# 05-USB-UART.net
KiCad netlist of a schematic drawn in Altium Designer
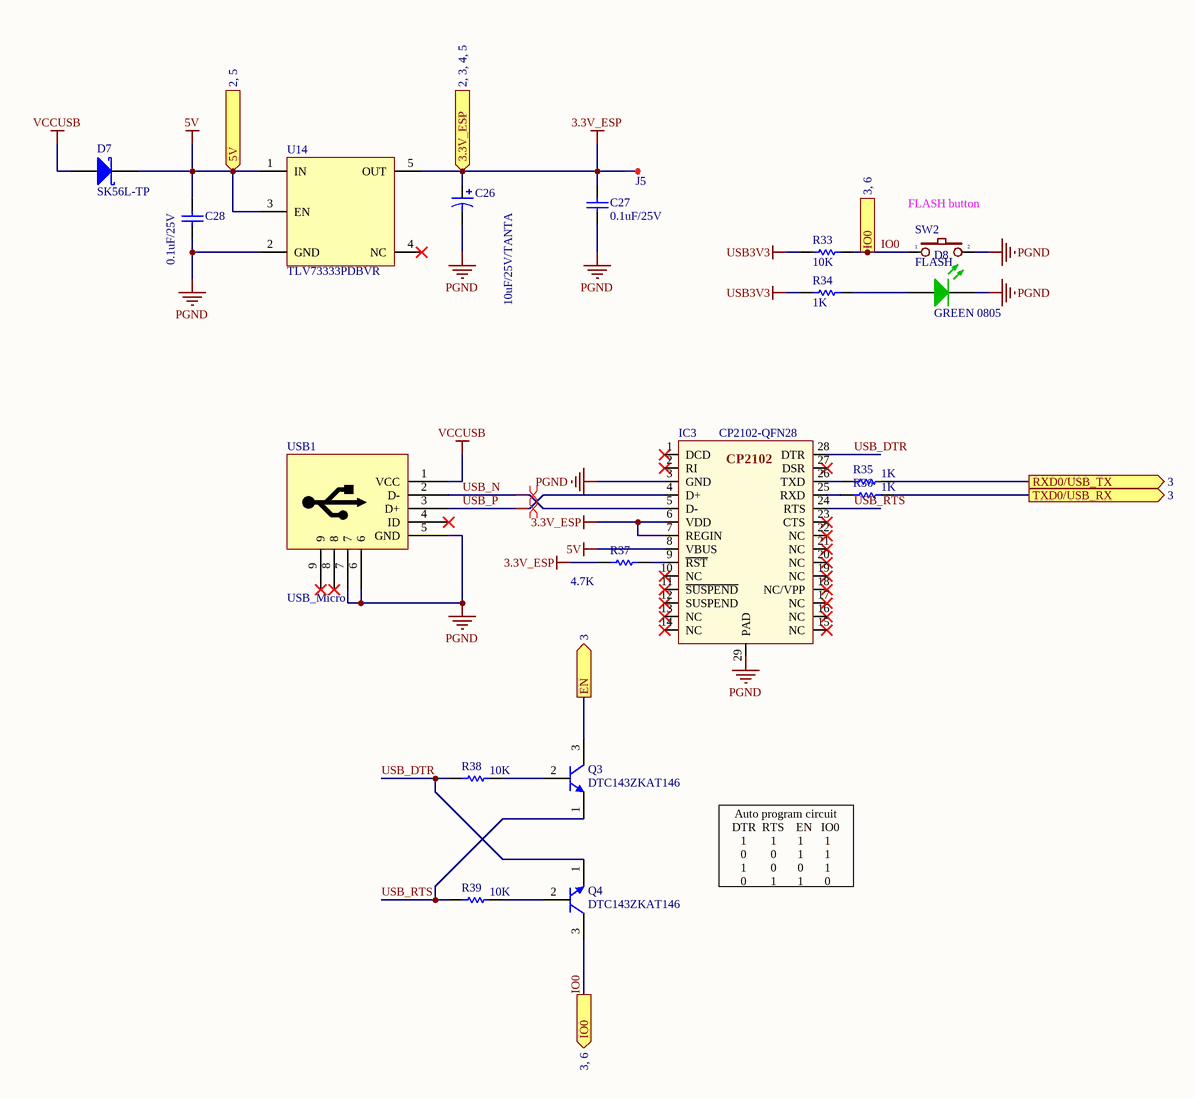
[diagram p0: 05-USB-UART.SchDoc]

(export (version "E")
  (design (tool "Eeschema 10.0.6"))
  (components
    (comp (ref "C26")
      (value "10uF/25V/TANTA")
      (footprint "CAP TANT CASE B SMD")
      (description "10µF Molded Tantalum Capacitors 25V 1411 (3528 Metric) 3 Ohm")
      (fields (field (name "MANUFACTURER") "KEMET"))
      (libsource (lib "GSHT_181013") (part "TAJB106M025RNJ"))
    )
    (comp (ref "C27")
      (value "0.1uF/25V")
      (footprint "CAP_CERA_C2012(CC0805INCH)")
      (description "0.1µF ±10% 25V Ceramic Capacitor X7R 0805 (2012 Metric)")
      (fields (field (name "MANUFACTURER") "KEMET"))
      (libsource (lib "GSHT_181013") (part "0.1uF/50V/C0603/10%"))
    )
    (comp (ref "C28")
      (value "0.1uF/25V")
      (footprint "CAP_CERA_C2012(CC0805INCH)")
      (description "0.1µF ±10% 25V Ceramic Capacitor X7R 0805 (2012 Metric)")
      (libsource (lib "GSHT_181013") (part "0.1uF/50V/C0603/10%"))
    )
    (comp (ref "D7")
      (value "SK56L-TP")
      (footprint "30# SK56L-TPMSCT-ND")
      (description "DIODE SCHOTTKY 60V 5A DO214AB")
      (libsource (lib "GSHT_181013") (part "30# SK56L-TP"))
    )
    (comp (ref "D8")
      (value "GREEN 0805")
      (footprint "Led 0805G")
      (description "Green 571nm LED Indication - Discrete 2V 0805 (2012 Metric)")
      (libsource (lib "GSHT_181013") (part "LED GREEN 0603"))
    )
    (comp (ref "IC3")
      (value "CP2102-QFN28")
      (footprint "CP2102-QFN28")
      (description "USB Bridge, USB to UART USB 2.0 UART Interface 28-QFN (5x5)")
      (libsource (lib "lpson") (part "CP2102"))
    )
    (comp (ref "J5")
      (value "TEST POINT")
      (footprint "TEST POINT 1mm")
      (description "TPoint")
      (libsource (lib "GSHT_181013") (part "PAD 1mm"))
    )
    (comp (ref "Q3")
      (value "DTC143ZKAT146")
      (footprint "6# DTC143ZKAT146-E")
      (description "Pre-Biased Bipolar Transistor (BJT) NPN - Pre-Biased 50V 100mA 250MHz 200mW Surface Mount SMT3")
      (libsource (lib "GSHT_181013") (part "6#DTC143ZKAT146"))
    )
    (comp (ref "Q4")
      (value "DTC143ZKAT146")
      (footprint "6# DTC143ZKAT146-E")
      (description "Pre-Biased Bipolar Transistor (BJT) NPN - Pre-Biased 50V 100mA 250MHz 200mW Surface Mount SMT3")
      (libsource (lib "GSHT_181013") (part "6#DTC143ZKAT146"))
    )
    (comp (ref "R33")
      (value "10K")
      (footprint "Res 0805 SMD")
      (description "10 kOhms ±1% 0.125W, 1/8W Chip Resistor 0805 (2012 Metric) Thick Film")
      (libsource (lib "GSHT_181013") (part "200K/R0603/1%"))
    )
    (comp (ref "R34")
      (value "1K")
      (footprint "Res 0805 SMD")
      (description "1 kOhms ±1% 0.125W, 1/8W Chip Resistor 0805 (2012 Metric) Automotive AEC-Q200 Thick Film")
      (libsource (lib "GSHT_181013") (part "200K/R0603/1%"))
    )
    (comp (ref "R35")
      (value "1K")
      (footprint "Res 0805 SMD")
      (description "1 kOhms ±1% 0.125W, 1/8W Chip Resistor 0805 (2012 Metric) Automotive AEC-Q200 Thick Film")
      (libsource (lib "GSHT_181013") (part "34.8K/R0805/1%"))
    )
    (comp (ref "R36")
      (value "1K")
      (footprint "Res 0805 SMD")
      (description "1 kOhms ±1% 0.125W, 1/8W Chip Resistor 0805 (2012 Metric) Automotive AEC-Q200 Thick Film")
      (libsource (lib "GSHT_181013") (part "34.8K/R0805/1%"))
    )
    (comp (ref "R37")
      (value "4.7K")
      (footprint "Res 0805 SMD")
      (description "4.7 kOhms ±1% 0.125W, 1/8W Chip Resistor 0805 (2012 Metric) Thick Film")
      (libsource (lib "GSHT_181013") (part "34.8K/R0805/1%"))
    )
    (comp (ref "R38")
      (value "10K")
      (footprint "Res 0805 SMD")
      (description "10 kOhms ±1% 0.125W, 1/8W Chip Resistor 0805 (2012 Metric) Thick Film")
      (libsource (lib "GSHT_181013") (part "34.8K/R0805/1%"))
    )
    (comp (ref "R39")
      (value "10K")
      (footprint "Res 0805 SMD")
      (description "10 kOhms ±1% 0.125W, 1/8W Chip Resistor 0805 (2012 Metric) Thick Film")
      (libsource (lib "GSHT_181013") (part "34.8K/R0805/1%"))
    )
    (comp (ref "SW2")
      (value "FLASH")
      (footprint "Button 3x4mm")
      (description "SWITCH TACTILE SPST-NO 0.05A 12V")
      (libsource (lib "lpson") (part "SW2"))
    )
    (comp (ref "U14")
      (value "TLV73333PDBVR")
      (footprint "20# TLV73333PDBVR")
      (description "Linear Voltage Regulator IC Positive Fixed 1 Output 3.3V 300mA SOT-23-5")
      (libsource (lib "GSHT_181013") (part "20#TLV73333PDBVR"))
    )
    (comp (ref "USB1")
      (value "USB_Micro")
      (footprint "USB_MICRO_B - Digikey")
      (description "USB - micro B USB 2.0 Receptacle Connector 5 Position Surface Mount, Right Angle; Through Hole")
      (libsource (lib "lpson") (part "USB_MINI"))
    )
  )
  (nets
    (net (code "1") (name "/EN") (class "Default")
      (node (ref "Q3") (pin "3") (pinfunction "C_3") (pintype "passive"))
    )
    (net (code "2") (name "/IO0") (class "Default")
      (node (ref "Q4") (pin "3") (pinfunction "C_3") (pintype "passive"))
      (node (ref "R33") (pin "2") (pinfunction "2_2") (pintype "passive"))
      (node (ref "SW2") (pin "1") (pinfunction "1_1") (pintype "passive"))
    )
    (net (code "3") (name "/RXD0{slash}USB_TX") (class "Default")
      (node (ref "R35") (pin "1") (pinfunction "1_1") (pintype "passive"))
    )
    (net (code "4") (name "/TXD0{slash}USB_RX") (class "Default")
      (node (ref "R36") (pin "1") (pinfunction "1_1") (pintype "passive"))
    )
    (net (code "5") (name "/USB_DTR") (class "Default")
      (node (ref "IC3") (pin "28") (pinfunction "DTR_28") (pintype "passive"))
      (node (ref "Q4") (pin "1") (pinfunction "E_1") (pintype "passive"))
      (node (ref "R38") (pin "2") (pinfunction "2_2") (pintype "passive"))
    )
    (net (code "6") (name "/USB_N") (class "Default")
      (node (ref "IC3") (pin "5") (pinfunction "D-_5") (pintype "passive"))
      (node (ref "USB1") (pin "2") (pinfunction "D-_2") (pintype "passive"))
    )
    (net (code "7") (name "/USB_P") (class "Default")
      (node (ref "IC3") (pin "4") (pinfunction "D+_4") (pintype "passive"))
      (node (ref "USB1") (pin "3") (pinfunction "D+_3") (pintype "passive"))
    )
    (net (code "8") (name "/USB_RTS") (class "Default")
      (node (ref "IC3") (pin "24") (pinfunction "RTS_24") (pintype "passive"))
      (node (ref "Q3") (pin "1") (pinfunction "E_1") (pintype "passive"))
      (node (ref "R39") (pin "2") (pinfunction "2_2") (pintype "passive"))
    )
    (net (code "9") (name "3.3V_ESP") (class "Default")
      (node (ref "C26") (pin "1") (pinfunction "1_1") (pintype "passive"))
      (node (ref "C27") (pin "2") (pinfunction "2_2") (pintype "passive"))
      (node (ref "IC3") (pin "6") (pinfunction "VDD_6") (pintype "passive"))
      (node (ref "IC3") (pin "7") (pinfunction "REGIN_7") (pintype "passive"))
      (node (ref "J5") (pin "1") (pinfunction "TP_1") (pintype "passive"))
      (node (ref "R37") (pin "1") (pinfunction "1_1") (pintype "passive"))
      (node (ref "U14") (pin "5") (pinfunction "OUT_5") (pintype "passive"))
    )
    (net (code "10") (name "5V") (class "Default")
      (node (ref "C28") (pin "2") (pinfunction "2_2") (pintype "passive"))
      (node (ref "D7") (pin "2") (pinfunction "K_2") (pintype "passive"))
      (node (ref "IC3") (pin "8") (pinfunction "VBUS_8") (pintype "passive"))
      (node (ref "U14") (pin "1") (pinfunction "IN_1") (pintype "passive"))
      (node (ref "U14") (pin "3") (pinfunction "EN_3") (pintype "passive"))
    )
    (net (code "11") (name "Net-(D8-A)") (class "Default")
      (node (ref "D8") (pin "1") (pinfunction "A_1") (pintype "passive"))
      (node (ref "R34") (pin "2") (pinfunction "2_2") (pintype "passive"))
    )
    (net (code "12") (name "Net-(IC3-RXD)") (class "Default")
      (node (ref "IC3") (pin "25") (pinfunction "RXD_25") (pintype "passive"))
      (node (ref "R36") (pin "2") (pinfunction "2_2") (pintype "passive"))
    )
    (net (code "13") (name "Net-(IC3-TXD)") (class "Default")
      (node (ref "IC3") (pin "26") (pinfunction "TXD_26") (pintype "passive"))
      (node (ref "R35") (pin "2") (pinfunction "2_2") (pintype "passive"))
    )
    (net (code "14") (name "Net-(IC3-~{RST})") (class "Default")
      (node (ref "IC3") (pin "9") (pinfunction "~{RST}_9") (pintype "passive"))
      (node (ref "R37") (pin "2") (pinfunction "2_2") (pintype "passive"))
    )
    (net (code "15") (name "Net-(Q3-B)") (class "Default")
      (node (ref "Q3") (pin "2") (pinfunction "B_2") (pintype "passive"))
      (node (ref "R38") (pin "1") (pinfunction "1_1") (pintype "passive"))
    )
    (net (code "16") (name "Net-(Q4-B)") (class "Default")
      (node (ref "Q4") (pin "2") (pinfunction "B_2") (pintype "passive"))
      (node (ref "R39") (pin "1") (pinfunction "1_1") (pintype "passive"))
    )
    (net (code "17") (name "PGND") (class "Default")
      (node (ref "C26") (pin "2") (pinfunction "2_2") (pintype "passive"))
      (node (ref "C27") (pin "1") (pinfunction "1_1") (pintype "passive"))
      (node (ref "C28") (pin "1") (pinfunction "1_1") (pintype "passive"))
      (node (ref "D8") (pin "2") (pinfunction "K_2") (pintype "passive"))
      (node (ref "IC3") (pin "29") (pinfunction "PAD_29") (pintype "passive"))
      (node (ref "IC3") (pin "3") (pinfunction "GND_3") (pintype "passive"))
      (node (ref "SW2") (pin "2") (pinfunction "2_2") (pintype "passive"))
      (node (ref "U14") (pin "2") (pinfunction "GND_2") (pintype "passive"))
      (node (ref "USB1") (pin "5") (pinfunction "GND_5") (pintype "passive"))
      (node (ref "USB1") (pin "6") (pinfunction "6_6") (pintype "passive"))
      (node (ref "USB1") (pin "7") (pinfunction "7_7") (pintype "passive"))
    )
    (net (code "18") (name "USB3V3") (class "Default")
      (node (ref "R33") (pin "1") (pinfunction "1_1") (pintype "passive"))
      (node (ref "R34") (pin "1") (pinfunction "1_1") (pintype "passive"))
    )
    (net (code "19") (name "VCCUSB") (class "Default")
      (node (ref "D7") (pin "1") (pinfunction "A_1") (pintype "passive"))
      (node (ref "USB1") (pin "1") (pinfunction "VCC_1") (pintype "passive"))
    )
    (net (code "20") (name "unconnected-(IC3-CTS-Pad23)") (class "Default")
      (node (ref "IC3") (pin "23") (pinfunction "CTS_23") (pintype "passive+no_connect"))
    )
    (net (code "21") (name "unconnected-(IC3-DCD-Pad1)") (class "Default")
      (node (ref "IC3") (pin "1") (pinfunction "DCD_1") (pintype "passive+no_connect"))
    )
    (net (code "22") (name "unconnected-(IC3-DSR-Pad27)") (class "Default")
      (node (ref "IC3") (pin "27") (pinfunction "DSR_27") (pintype "passive+no_connect"))
    )
    (net (code "23") (name "unconnected-(IC3-NC-Pad10)") (class "Default")
      (node (ref "IC3") (pin "10") (pinfunction "NC_10") (pintype "passive+no_connect"))
    )
    (net (code "24") (name "unconnected-(IC3-NC-Pad13)") (class "Default")
      (node (ref "IC3") (pin "13") (pinfunction "NC_13") (pintype "passive+no_connect"))
    )
    (net (code "25") (name "unconnected-(IC3-NC-Pad14)") (class "Default")
      (node (ref "IC3") (pin "14") (pinfunction "NC_14") (pintype "passive+no_connect"))
    )
    (net (code "26") (name "unconnected-(IC3-NC-Pad15)") (class "Default")
      (node (ref "IC3") (pin "15") (pinfunction "NC_15") (pintype "passive+no_connect"))
    )
    (net (code "27") (name "unconnected-(IC3-NC-Pad16)") (class "Default")
      (node (ref "IC3") (pin "16") (pinfunction "NC_16") (pintype "passive+no_connect"))
    )
    (net (code "28") (name "unconnected-(IC3-NC-Pad17)") (class "Default")
      (node (ref "IC3") (pin "17") (pinfunction "NC_17") (pintype "passive+no_connect"))
    )
    (net (code "29") (name "unconnected-(IC3-NC-Pad19)") (class "Default")
      (node (ref "IC3") (pin "19") (pinfunction "NC_19") (pintype "passive+no_connect"))
    )
    (net (code "30") (name "unconnected-(IC3-NC-Pad20)") (class "Default")
      (node (ref "IC3") (pin "20") (pinfunction "NC_20") (pintype "passive+no_connect"))
    )
    (net (code "31") (name "unconnected-(IC3-NC-Pad21)") (class "Default")
      (node (ref "IC3") (pin "21") (pinfunction "NC_21") (pintype "passive+no_connect"))
    )
    (net (code "32") (name "unconnected-(IC3-NC-Pad22)") (class "Default")
      (node (ref "IC3") (pin "22") (pinfunction "NC_22") (pintype "passive+no_connect"))
    )
    (net (code "33") (name "unconnected-(IC3-NC{slash}VPP-Pad18)") (class "Default")
      (node (ref "IC3") (pin "18") (pinfunction "NC/VPP_18") (pintype "passive+no_connect"))
    )
    (net (code "34") (name "unconnected-(IC3-RI-Pad2)") (class "Default")
      (node (ref "IC3") (pin "2") (pinfunction "RI_2") (pintype "passive+no_connect"))
    )
    (net (code "35") (name "unconnected-(IC3-SUSPEND-Pad12)") (class "Default")
      (node (ref "IC3") (pin "12") (pinfunction "SUSPEND_12") (pintype "passive+no_connect"))
    )
    (net (code "36") (name "unconnected-(IC3-~{SUSPEND}-Pad11)") (class "Default")
      (node (ref "IC3") (pin "11") (pinfunction "~{SUSPEND}_11") (pintype "passive+no_connect"))
    )
    (net (code "37") (name "unconnected-(U14-NC-Pad4)") (class "Default")
      (node (ref "U14") (pin "4") (pinfunction "NC_4") (pintype "passive+no_connect"))
    )
    (net (code "38") (name "unconnected-(USB1-ID-Pad4)") (class "Default")
      (node (ref "USB1") (pin "4") (pinfunction "ID_4") (pintype "passive+no_connect"))
    )
    (net (code "39") (name "unconnected-(USB1-Pad8)") (class "Default")
      (node (ref "USB1") (pin "8") (pinfunction "8_8") (pintype "passive+no_connect"))
    )
    (net (code "40") (name "unconnected-(USB1-Pad9)") (class "Default")
      (node (ref "USB1") (pin "9") (pinfunction "9_9") (pintype "passive+no_connect"))
    )
  )
)
